# Base_logic_gate.net
KiCad netlist of a schematic drawn in Altium Designer
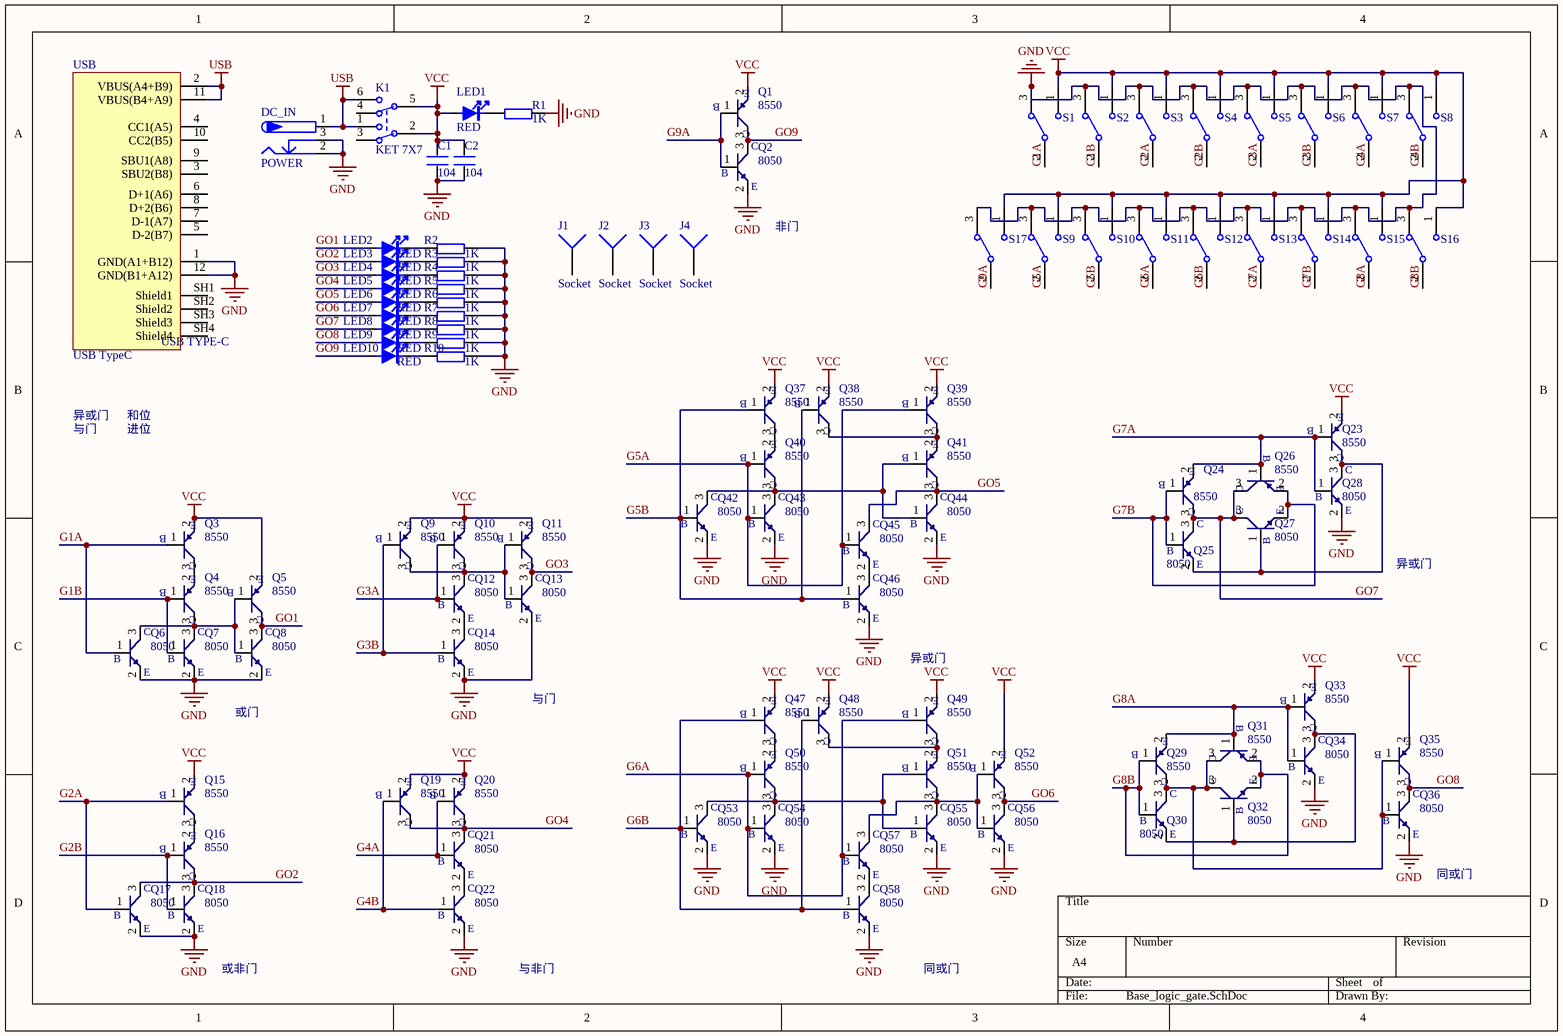
[diagram p0: Base_logic_gate.SchDoc]

(export (version "E")
  (design (tool "Eeschema 10.0.6"))
  (components
    (comp (ref "C1")
      (value "104")
      (footprint "C 0603_L")
      (libsource (lib "IMX6UL_ALPHA(底板)_V2.0") (part "C"))
    )
    (comp (ref "C2")
      (value "104")
      (footprint "C 0603_L")
      (libsource (lib "IMX6UL_ALPHA(底板)_V2.0") (part "C"))
    )
    (comp (ref "DC_IN")
      (value "POWER")
      (footprint "DC-005")
      (description "低压电源接口")
      (fields (field (name "版权归属") "源创客"))
      (libsource (lib "IMX6UL_ALPHA(底板)_V2.0") (part "P-DC"))
    )
    (comp (ref "J1")
      (value "Socket")
      (footprint "M3")
      (fields (field (name "PUBLISHER") "Altium Limited"))
      (libsource (lib "Miscellaneous Connectors") (part "Socket"))
    )
    (comp (ref "J2")
      (value "Socket")
      (footprint "M3")
      (fields (field (name "PUBLISHER") "Altium Limited"))
      (libsource (lib "Miscellaneous Connectors") (part "Socket"))
    )
    (comp (ref "J3")
      (value "Socket")
      (footprint "M3")
      (fields (field (name "PUBLISHER") "Altium Limited"))
      (libsource (lib "Miscellaneous Connectors") (part "Socket"))
    )
    (comp (ref "J4")
      (value "Socket")
      (footprint "M3")
      (fields (field (name "PUBLISHER") "Altium Limited"))
      (libsource (lib "Miscellaneous Connectors") (part "Socket"))
    )
    (comp (ref "K1")
      (value "KET 7X7")
      (footprint "KFT DIP-8X8")
      (description "7*7自锁开关")
      (fields (field (name "版权归属") "正点原子"))
      (libsource (lib "正点原子封装库V1.0") (part "KET 7X7"))
    )
    (comp (ref "LED1")
      (value "RED")
      (footprint "LED 0603B")
      (description "发光二极管")
      (libsource (lib "LovelessingSch") (part "LED"))
    )
    (comp (ref "LED2")
      (value "RED")
      (footprint "LED 0603B")
      (description "发光二极管")
      (libsource (lib "LovelessingSch") (part "LED"))
    )
    (comp (ref "LED3")
      (value "RED")
      (footprint "LED 0603B")
      (description "发光二极管")
      (libsource (lib "LovelessingSch") (part "LED"))
    )
    (comp (ref "LED4")
      (value "RED")
      (footprint "LED 0603B")
      (description "发光二极管")
      (libsource (lib "LovelessingSch") (part "LED"))
    )
    (comp (ref "LED5")
      (value "RED")
      (footprint "LED 0603B")
      (description "发光二极管")
      (libsource (lib "LovelessingSch") (part "LED"))
    )
    (comp (ref "LED6")
      (value "RED")
      (footprint "LED 0603B")
      (description "发光二极管")
      (libsource (lib "LovelessingSch") (part "LED"))
    )
    (comp (ref "LED7")
      (value "RED")
      (footprint "LED 0603B")
      (description "发光二极管")
      (libsource (lib "LovelessingSch") (part "LED"))
    )
    (comp (ref "LED8")
      (value "RED")
      (footprint "LED 0603B")
      (description "发光二极管")
      (libsource (lib "LovelessingSch") (part "LED"))
    )
    (comp (ref "LED9")
      (value "RED")
      (footprint "LED 0603B")
      (description "发光二极管")
      (libsource (lib "LovelessingSch") (part "LED"))
    )
    (comp (ref "LED10")
      (value "RED")
      (footprint "LED 0603B")
      (description "发光二极管")
      (libsource (lib "LovelessingSch") (part "LED"))
    )
    (comp (ref "Q1")
      (value "8550")
      (footprint "SOT23-3L")
      (libsource (lib "LovelessingSch") (part "8550PNP"))
    )
    (comp (ref "Q2")
      (value "8050")
      (footprint "SOT23-3L")
      (libsource (lib "LovelessingSch") (part "8050NPN"))
    )
    (comp (ref "Q3")
      (value "8550")
      (footprint "SOT23-3L")
      (libsource (lib "LovelessingSch") (part "8550PNP"))
    )
    (comp (ref "Q4")
      (value "8550")
      (footprint "SOT23-3L")
      (libsource (lib "LovelessingSch") (part "8550PNP"))
    )
    (comp (ref "Q5")
      (value "8550")
      (footprint "SOT23-3L")
      (libsource (lib "LovelessingSch") (part "8550PNP"))
    )
    (comp (ref "Q6")
      (value "8050")
      (footprint "SOT23-3L")
      (libsource (lib "LovelessingSch") (part "8050NPN"))
    )
    (comp (ref "Q7")
      (value "8050")
      (footprint "SOT23-3L")
      (libsource (lib "LovelessingSch") (part "8050NPN"))
    )
    (comp (ref "Q8")
      (value "8050")
      (footprint "SOT23-3L")
      (libsource (lib "LovelessingSch") (part "8050NPN"))
    )
    (comp (ref "Q9")
      (value "8550")
      (footprint "SOT23-3L")
      (libsource (lib "LovelessingSch") (part "8550PNP"))
    )
    (comp (ref "Q10")
      (value "8550")
      (footprint "SOT23-3L")
      (libsource (lib "LovelessingSch") (part "8550PNP"))
    )
    (comp (ref "Q11")
      (value "8550")
      (footprint "SOT23-3L")
      (libsource (lib "LovelessingSch") (part "8550PNP"))
    )
    (comp (ref "Q12")
      (value "8050")
      (footprint "SOT23-3L")
      (libsource (lib "LovelessingSch") (part "8050NPN"))
    )
    (comp (ref "Q13")
      (value "8050")
      (footprint "SOT23-3L")
      (libsource (lib "LovelessingSch") (part "8050NPN"))
    )
    (comp (ref "Q14")
      (value "8050")
      (footprint "SOT23-3L")
      (libsource (lib "LovelessingSch") (part "8050NPN"))
    )
    (comp (ref "Q15")
      (value "8550")
      (footprint "SOT23-3L")
      (libsource (lib "LovelessingSch") (part "8550PNP"))
    )
    (comp (ref "Q16")
      (value "8550")
      (footprint "SOT23-3L")
      (libsource (lib "LovelessingSch") (part "8550PNP"))
    )
    (comp (ref "Q17")
      (value "8050")
      (footprint "SOT23-3L")
      (libsource (lib "LovelessingSch") (part "8050NPN"))
    )
    (comp (ref "Q18")
      (value "8050")
      (footprint "SOT23-3L")
      (libsource (lib "LovelessingSch") (part "8050NPN"))
    )
    (comp (ref "Q19")
      (value "8550")
      (footprint "SOT23-3L")
      (libsource (lib "LovelessingSch") (part "8550PNP"))
    )
    (comp (ref "Q20")
      (value "8550")
      (footprint "SOT23-3L")
      (libsource (lib "LovelessingSch") (part "8550PNP"))
    )
    (comp (ref "Q21")
      (value "8050")
      (footprint "SOT23-3L")
      (libsource (lib "LovelessingSch") (part "8050NPN"))
    )
    (comp (ref "Q22")
      (value "8050")
      (footprint "SOT23-3L")
      (libsource (lib "LovelessingSch") (part "8050NPN"))
    )
    (comp (ref "Q23")
      (value "8550")
      (footprint "SOT23-3L")
      (libsource (lib "LovelessingSch") (part "8550PNP"))
    )
    (comp (ref "Q24")
      (value "8550")
      (footprint "SOT23-3L")
      (libsource (lib "LovelessingSch") (part "8550PNP"))
    )
    (comp (ref "Q25")
      (value "8050")
      (footprint "SOT23-3L")
      (libsource (lib "LovelessingSch") (part "8050NPN"))
    )
    (comp (ref "Q26")
      (value "8550")
      (footprint "SOT23-3L")
      (libsource (lib "LovelessingSch") (part "8550PNP"))
    )
    (comp (ref "Q27")
      (value "8050")
      (footprint "SOT23-3L")
      (libsource (lib "LovelessingSch") (part "8050NPN"))
    )
    (comp (ref "Q28")
      (value "8050")
      (footprint "SOT23-3L")
      (libsource (lib "LovelessingSch") (part "8050NPN"))
    )
    (comp (ref "Q29")
      (value "8550")
      (footprint "SOT23-3L")
      (libsource (lib "LovelessingSch") (part "8550PNP"))
    )
    (comp (ref "Q30")
      (value "8050")
      (footprint "SOT23-3L")
      (libsource (lib "LovelessingSch") (part "8050NPN"))
    )
    (comp (ref "Q31")
      (value "8550")
      (footprint "SOT23-3L")
      (libsource (lib "LovelessingSch") (part "8550PNP"))
    )
    (comp (ref "Q32")
      (value "8050")
      (footprint "SOT23-3L")
      (libsource (lib "LovelessingSch") (part "8050NPN"))
    )
    (comp (ref "Q33")
      (value "8550")
      (footprint "SOT23-3L")
      (libsource (lib "LovelessingSch") (part "8550PNP"))
    )
    (comp (ref "Q34")
      (value "8050")
      (footprint "SOT23-3L")
      (libsource (lib "LovelessingSch") (part "8050NPN"))
    )
    (comp (ref "Q35")
      (value "8550")
      (footprint "SOT23-3L")
      (libsource (lib "LovelessingSch") (part "8550PNP"))
    )
    (comp (ref "Q36")
      (value "8050")
      (footprint "SOT23-3L")
      (libsource (lib "LovelessingSch") (part "8050NPN"))
    )
    (comp (ref "Q37")
      (value "8550")
      (footprint "SOT23-3L")
      (libsource (lib "LovelessingSch") (part "8550PNP"))
    )
    (comp (ref "Q38")
      (value "8550")
      (footprint "SOT23-3L")
      (libsource (lib "LovelessingSch") (part "8550PNP"))
    )
    (comp (ref "Q39")
      (value "8550")
      (footprint "SOT23-3L")
      (libsource (lib "LovelessingSch") (part "8550PNP"))
    )
    (comp (ref "Q40")
      (value "8550")
      (footprint "SOT23-3L")
      (libsource (lib "LovelessingSch") (part "8550PNP"))
    )
    (comp (ref "Q41")
      (value "8550")
      (footprint "SOT23-3L")
      (libsource (lib "LovelessingSch") (part "8550PNP"))
    )
    (comp (ref "Q42")
      (value "8050")
      (footprint "SOT23-3L")
      (libsource (lib "LovelessingSch") (part "8050NPN"))
    )
    (comp (ref "Q43")
      (value "8050")
      (footprint "SOT23-3L")
      (libsource (lib "LovelessingSch") (part "8050NPN"))
    )
    (comp (ref "Q44")
      (value "8050")
      (footprint "SOT23-3L")
      (libsource (lib "LovelessingSch") (part "8050NPN"))
    )
    (comp (ref "Q45")
      (value "8050")
      (footprint "SOT23-3L")
      (libsource (lib "LovelessingSch") (part "8050NPN"))
    )
    (comp (ref "Q46")
      (value "8050")
      (footprint "SOT23-3L")
      (libsource (lib "LovelessingSch") (part "8050NPN"))
    )
    (comp (ref "Q47")
      (value "8550")
      (footprint "SOT23-3L")
      (libsource (lib "LovelessingSch") (part "8550PNP"))
    )
    (comp (ref "Q48")
      (value "8550")
      (footprint "SOT23-3L")
      (libsource (lib "LovelessingSch") (part "8550PNP"))
    )
    (comp (ref "Q49")
      (value "8550")
      (footprint "SOT23-3L")
      (libsource (lib "LovelessingSch") (part "8550PNP"))
    )
    (comp (ref "Q50")
      (value "8550")
      (footprint "SOT23-3L")
      (libsource (lib "LovelessingSch") (part "8550PNP"))
    )
    (comp (ref "Q51")
      (value "8550")
      (footprint "SOT23-3L")
      (libsource (lib "LovelessingSch") (part "8550PNP"))
    )
    (comp (ref "Q52")
      (value "8550")
      (footprint "SOT23-3L")
      (libsource (lib "LovelessingSch") (part "8550PNP"))
    )
    (comp (ref "Q53")
      (value "8050")
      (footprint "SOT23-3L")
      (libsource (lib "LovelessingSch") (part "8050NPN"))
    )
    (comp (ref "Q54")
      (value "8050")
      (footprint "SOT23-3L")
      (libsource (lib "LovelessingSch") (part "8050NPN"))
    )
    (comp (ref "Q55")
      (value "8050")
      (footprint "SOT23-3L")
      (libsource (lib "LovelessingSch") (part "8050NPN"))
    )
    (comp (ref "Q56")
      (value "8050")
      (footprint "SOT23-3L")
      (libsource (lib "LovelessingSch") (part "8050NPN"))
    )
    (comp (ref "Q57")
      (value "8050")
      (footprint "SOT23-3L")
      (libsource (lib "LovelessingSch") (part "8050NPN"))
    )
    (comp (ref "Q58")
      (value "8050")
      (footprint "SOT23-3L")
      (libsource (lib "LovelessingSch") (part "8050NPN"))
    )
    (comp (ref "R1") (value "1K") (footprint "R 0603_L") (libsource (lib "IMX6UL_ALPHA(底板)_V2.0") (part "R")))
    (comp (ref "R2") (value "1K") (footprint "R 0603_L") (libsource (lib "IMX6UL_ALPHA(底板)_V2.0") (part "R")))
    (comp (ref "R3") (value "1K") (footprint "R 0603_L") (libsource (lib "IMX6UL_ALPHA(底板)_V2.0") (part "R")))
    (comp (ref "R4") (value "1K") (footprint "R 0603_L") (libsource (lib "IMX6UL_ALPHA(底板)_V2.0") (part "R")))
    (comp (ref "R5") (value "1K") (footprint "R 0603_L") (libsource (lib "IMX6UL_ALPHA(底板)_V2.0") (part "R")))
    (comp (ref "R6") (value "1K") (footprint "R 0603_L") (libsource (lib "IMX6UL_ALPHA(底板)_V2.0") (part "R")))
    (comp (ref "R7") (value "1K") (footprint "R 0603_L") (libsource (lib "IMX6UL_ALPHA(底板)_V2.0") (part "R")))
    (comp (ref "R8") (value "1K") (footprint "R 0603_L") (libsource (lib "IMX6UL_ALPHA(底板)_V2.0") (part "R")))
    (comp (ref "R9") (value "1K") (footprint "R 0603_L") (libsource (lib "IMX6UL_ALPHA(底板)_V2.0") (part "R")))
    (comp (ref "R10")
      (value "1K")
      (footprint "R 0603_L")
      (libsource (lib "IMX6UL_ALPHA(底板)_V2.0") (part "R"))
    )
    (comp (ref "S1")
      (value "BUTTON_DIP3")
      (footprint "BTN8.8*4.6")
      (description "SPDT Subminiature Toggle Switch, Right Angle Mounting, Vertical Actuation")
      (fields (field (name "PUBLISHER") "Altium Limited"))
      (libsource (lib "Miscellaneous Devices") (part "SW-SPDT"))
    )
    (comp (ref "S2")
      (value "BUTTON_DIP3")
      (footprint "BTN8.8*4.6")
      (description "SPDT Subminiature Toggle Switch, Right Angle Mounting, Vertical Actuation")
      (fields (field (name "PUBLISHER") "Altium Limited"))
      (libsource (lib "Miscellaneous Devices") (part "SW-SPDT"))
    )
    (comp (ref "S3")
      (value "BUTTON_DIP3")
      (footprint "BTN8.8*4.6")
      (description "SPDT Subminiature Toggle Switch, Right Angle Mounting, Vertical Actuation")
      (fields (field (name "PUBLISHER") "Altium Limited"))
      (libsource (lib "Miscellaneous Devices") (part "SW-SPDT"))
    )
    (comp (ref "S4")
      (value "BUTTON_DIP3")
      (footprint "BTN8.8*4.6")
      (description "SPDT Subminiature Toggle Switch, Right Angle Mounting, Vertical Actuation")
      (fields (field (name "PUBLISHER") "Altium Limited"))
      (libsource (lib "Miscellaneous Devices") (part "SW-SPDT"))
    )
    (comp (ref "S5")
      (value "BUTTON_DIP3")
      (footprint "BTN8.8*4.6")
      (description "SPDT Subminiature Toggle Switch, Right Angle Mounting, Vertical Actuation")
      (fields (field (name "PUBLISHER") "Altium Limited"))
      (libsource (lib "Miscellaneous Devices") (part "SW-SPDT"))
    )
    (comp (ref "S6")
      (value "BUTTON_DIP3")
      (footprint "BTN8.8*4.6")
      (description "SPDT Subminiature Toggle Switch, Right Angle Mounting, Vertical Actuation")
      (fields (field (name "PUBLISHER") "Altium Limited"))
      (libsource (lib "Miscellaneous Devices") (part "SW-SPDT"))
    )
    (comp (ref "S7")
      (value "BUTTON_DIP3")
      (footprint "BTN8.8*4.6")
      (description "SPDT Subminiature Toggle Switch, Right Angle Mounting, Vertical Actuation")
      (fields (field (name "PUBLISHER") "Altium Limited"))
      (libsource (lib "Miscellaneous Devices") (part "SW-SPDT"))
    )
    (comp (ref "S8")
      (value "BUTTON_DIP3")
      (footprint "BTN8.8*4.6")
      (description "SPDT Subminiature Toggle Switch, Right Angle Mounting, Vertical Actuation")
      (fields (field (name "PUBLISHER") "Altium Limited"))
      (libsource (lib "Miscellaneous Devices") (part "SW-SPDT"))
    )
    (comp (ref "S9")
      (value "BUTTON_DIP3")
      (footprint "BTN8.8*4.6")
      (description "SPDT Subminiature Toggle Switch, Right Angle Mounting, Vertical Actuation")
      (fields (field (name "PUBLISHER") "Altium Limited"))
      (libsource (lib "Miscellaneous Devices") (part "SW-SPDT"))
    )
    (comp (ref "S10")
      (value "BUTTON_DIP3")
      (footprint "BTN8.8*4.6")
      (description "SPDT Subminiature Toggle Switch, Right Angle Mounting, Vertical Actuation")
      (fields (field (name "PUBLISHER") "Altium Limited"))
      (libsource (lib "Miscellaneous Devices") (part "SW-SPDT"))
    )
    (comp (ref "S11")
      (value "BUTTON_DIP3")
      (footprint "BTN8.8*4.6")
      (description "SPDT Subminiature Toggle Switch, Right Angle Mounting, Vertical Actuation")
      (fields (field (name "PUBLISHER") "Altium Limited"))
      (libsource (lib "Miscellaneous Devices") (part "SW-SPDT"))
    )
    (comp (ref "S12")
      (value "BUTTON_DIP3")
      (footprint "BTN8.8*4.6")
      (description "SPDT Subminiature Toggle Switch, Right Angle Mounting, Vertical Actuation")
      (fields (field (name "PUBLISHER") "Altium Limited"))
      (libsource (lib "Miscellaneous Devices") (part "SW-SPDT"))
    )
    (comp (ref "S13")
      (value "BUTTON_DIP3")
      (footprint "BTN8.8*4.6")
      (description "SPDT Subminiature Toggle Switch, Right Angle Mounting, Vertical Actuation")
      (fields (field (name "PUBLISHER") "Altium Limited"))
      (libsource (lib "Miscellaneous Devices") (part "SW-SPDT"))
    )
    (comp (ref "S14")
      (value "BUTTON_DIP3")
      (footprint "BTN8.8*4.6")
      (description "SPDT Subminiature Toggle Switch, Right Angle Mounting, Vertical Actuation")
      (fields (field (name "PUBLISHER") "Altium Limited"))
      (libsource (lib "Miscellaneous Devices") (part "SW-SPDT"))
    )
    (comp (ref "S15")
      (value "BUTTON_DIP3")
      (footprint "BTN8.8*4.6")
      (description "SPDT Subminiature Toggle Switch, Right Angle Mounting, Vertical Actuation")
      (fields (field (name "PUBLISHER") "Altium Limited"))
      (libsource (lib "Miscellaneous Devices") (part "SW-SPDT"))
    )
    (comp (ref "S16")
      (value "BUTTON_DIP3")
      (footprint "BTN8.8*4.6")
      (description "SPDT Subminiature Toggle Switch, Right Angle Mounting, Vertical Actuation")
      (fields (field (name "PUBLISHER") "Altium Limited"))
      (libsource (lib "Miscellaneous Devices") (part "SW-SPDT"))
    )
    (comp (ref "S17")
      (value "BUTTON_DIP3")
      (footprint "BTN8.8*4.6")
      (description "SPDT Subminiature Toggle Switch, Right Angle Mounting, Vertical Actuation")
      (fields (field (name "PUBLISHER") "Altium Limited"))
      (libsource (lib "Miscellaneous Devices") (part "SW-SPDT"))
    )
    (comp (ref "USB")
      (value "USB TypeC")
      (footprint "USB Type-C")
      (description "12P TypeC 母座")
      (fields (field (name "版权归属") "正点原子"))
      (libsource (lib "正点原子封装库V1.0") (part "USB 2.0 Type C"))
    )
  )
  (nets
    (net (code "1") (name "/G1A") (class "Default")
      (node (ref "Q3") (pin "1") (pinfunction "B_1") (pintype "passive"))
      (node (ref "Q6") (pin "1") (pinfunction "B_1") (pintype "passive"))
      (node (ref "S1") (pin "2") (pinfunction "2_2") (pintype "passive"))
    )
    (net (code "2") (name "/G1B") (class "Default")
      (node (ref "Q4") (pin "1") (pinfunction "B_1") (pintype "passive"))
      (node (ref "Q7") (pin "1") (pinfunction "B_1") (pintype "passive"))
      (node (ref "S2") (pin "2") (pinfunction "2_2") (pintype "passive"))
    )
    (net (code "3") (name "/G2A") (class "Default")
      (node (ref "Q15") (pin "1") (pinfunction "B_1") (pintype "passive"))
      (node (ref "Q17") (pin "1") (pinfunction "B_1") (pintype "passive"))
      (node (ref "S3") (pin "2") (pinfunction "2_2") (pintype "passive"))
    )
    (net (code "4") (name "/G2B") (class "Default")
      (node (ref "Q16") (pin "1") (pinfunction "B_1") (pintype "passive"))
      (node (ref "Q18") (pin "1") (pinfunction "B_1") (pintype "passive"))
      (node (ref "S4") (pin "2") (pinfunction "2_2") (pintype "passive"))
    )
    (net (code "5") (name "/G3A") (class "Default")
      (node (ref "Q10") (pin "1") (pinfunction "B_1") (pintype "passive"))
      (node (ref "Q12") (pin "1") (pinfunction "B_1") (pintype "passive"))
      (node (ref "S5") (pin "2") (pinfunction "2_2") (pintype "passive"))
    )
    (net (code "6") (name "/G3B") (class "Default")
      (node (ref "Q14") (pin "1") (pinfunction "B_1") (pintype "passive"))
      (node (ref "Q9") (pin "1") (pinfunction "B_1") (pintype "passive"))
      (node (ref "S6") (pin "2") (pinfunction "2_2") (pintype "passive"))
    )
    (net (code "7") (name "/G4A") (class "Default")
      (node (ref "Q20") (pin "1") (pinfunction "B_1") (pintype "passive"))
      (node (ref "Q21") (pin "1") (pinfunction "B_1") (pintype "passive"))
      (node (ref "S7") (pin "2") (pinfunction "2_2") (pintype "passive"))
    )
    (net (code "8") (name "/G4B") (class "Default")
      (node (ref "Q19") (pin "1") (pinfunction "B_1") (pintype "passive"))
      (node (ref "Q22") (pin "1") (pinfunction "B_1") (pintype "passive"))
      (node (ref "S8") (pin "2") (pinfunction "2_2") (pintype "passive"))
    )
    (net (code "9") (name "/G5A") (class "Default")
      (node (ref "Q39") (pin "1") (pinfunction "B_1") (pintype "passive"))
      (node (ref "Q40") (pin "1") (pinfunction "B_1") (pintype "passive"))
      (node (ref "Q43") (pin "1") (pinfunction "B_1") (pintype "passive"))
      (node (ref "Q45") (pin "1") (pinfunction "B_1") (pintype "passive"))
      (node (ref "S9") (pin "2") (pinfunction "2_2") (pintype "passive"))
    )
    (net (code "10") (name "/G5B") (class "Default")
      (node (ref "Q37") (pin "1") (pinfunction "B_1") (pintype "passive"))
      (node (ref "Q38") (pin "1") (pinfunction "B_1") (pintype "passive"))
      (node (ref "Q42") (pin "1") (pinfunction "B_1") (pintype "passive"))
      (node (ref "Q46") (pin "1") (pinfunction "B_1") (pintype "passive"))
      (node (ref "S10") (pin "2") (pinfunction "2_2") (pintype "passive"))
    )
    (net (code "11") (name "/G6A") (class "Default")
      (node (ref "Q49") (pin "1") (pinfunction "B_1") (pintype "passive"))
      (node (ref "Q50") (pin "1") (pinfunction "B_1") (pintype "passive"))
      (node (ref "Q54") (pin "1") (pinfunction "B_1") (pintype "passive"))
      (node (ref "Q57") (pin "1") (pinfunction "B_1") (pintype "passive"))
      (node (ref "S11") (pin "2") (pinfunction "2_2") (pintype "passive"))
    )
    (net (code "12") (name "/G6B") (class "Default")
      (node (ref "Q47") (pin "1") (pinfunction "B_1") (pintype "passive"))
      (node (ref "Q48") (pin "1") (pinfunction "B_1") (pintype "passive"))
      (node (ref "Q53") (pin "1") (pinfunction "B_1") (pintype "passive"))
      (node (ref "Q58") (pin "1") (pinfunction "B_1") (pintype "passive"))
      (node (ref "S12") (pin "2") (pinfunction "2_2") (pintype "passive"))
    )
    (net (code "13") (name "/G7A") (class "Default")
      (node (ref "Q23") (pin "1") (pinfunction "B_1") (pintype "passive"))
      (node (ref "Q24") (pin "2") (pinfunction "E_2") (pintype "passive"))
      (node (ref "Q26") (pin "1") (pinfunction "B_1") (pintype "passive"))
      (node (ref "Q28") (pin "1") (pinfunction "B_1") (pintype "passive"))
      (node (ref "S13") (pin "2") (pinfunction "2_2") (pintype "passive"))
    )
    (net (code "14") (name "/G7B") (class "Default")
      (node (ref "Q24") (pin "1") (pinfunction "B_1") (pintype "passive"))
      (node (ref "Q25") (pin "1") (pinfunction "B_1") (pintype "passive"))
      (node (ref "Q26") (pin "2") (pinfunction "E_2") (pintype "passive"))
      (node (ref "Q27") (pin "2") (pinfunction "E_2") (pintype "passive"))
      (node (ref "S14") (pin "2") (pinfunction "2_2") (pintype "passive"))
    )
    (net (code "15") (name "/G8A") (class "Default")
      (node (ref "Q29") (pin "2") (pinfunction "E_2") (pintype "passive"))
      (node (ref "Q31") (pin "1") (pinfunction "B_1") (pintype "passive"))
      (node (ref "Q33") (pin "1") (pinfunction "B_1") (pintype "passive"))
      (node (ref "Q34") (pin "1") (pinfunction "B_1") (pintype "passive"))
      (node (ref "S15") (pin "2") (pinfunction "2_2") (pintype "passive"))
    )
    (net (code "16") (name "/G8B") (class "Default")
      (node (ref "Q29") (pin "1") (pinfunction "B_1") (pintype "passive"))
      (node (ref "Q30") (pin "1") (pinfunction "B_1") (pintype "passive"))
      (node (ref "Q31") (pin "2") (pinfunction "E_2") (pintype "passive"))
      (node (ref "Q32") (pin "2") (pinfunction "E_2") (pintype "passive"))
      (node (ref "S16") (pin "2") (pinfunction "2_2") (pintype "passive"))
    )
    (net (code "17") (name "/G9A") (class "Default")
      (node (ref "Q1") (pin "1") (pinfunction "B_1") (pintype "passive"))
      (node (ref "Q2") (pin "1") (pinfunction "B_1") (pintype "passive"))
      (node (ref "S17") (pin "2") (pinfunction "2_2") (pintype "passive"))
    )
    (net (code "18") (name "/GO1") (class "Default")
      (node (ref "LED2") (pin "1") (pinfunction "1_1") (pintype "passive"))
      (node (ref "Q5") (pin "3") (pinfunction "C_3") (pintype "passive"))
      (node (ref "Q8") (pin "3") (pinfunction "C_3") (pintype "passive"))
    )
    (net (code "19") (name "/GO2") (class "Default")
      (node (ref "LED3") (pin "1") (pinfunction "1_1") (pintype "passive"))
      (node (ref "Q16") (pin "3") (pinfunction "C_3") (pintype "passive"))
      (node (ref "Q17") (pin "3") (pinfunction "C_3") (pintype "passive"))
      (node (ref "Q18") (pin "3") (pinfunction "C_3") (pintype "passive"))
    )
    (net (code "20") (name "/GO3") (class "Default")
      (node (ref "LED4") (pin "1") (pinfunction "1_1") (pintype "passive"))
      (node (ref "Q11") (pin "3") (pinfunction "C_3") (pintype "passive"))
      (node (ref "Q13") (pin "3") (pinfunction "C_3") (pintype "passive"))
    )
    (net (code "21") (name "/GO4") (class "Default")
      (node (ref "LED5") (pin "1") (pinfunction "1_1") (pintype "passive"))
      (node (ref "Q19") (pin "3") (pinfunction "C_3") (pintype "passive"))
      (node (ref "Q20") (pin "3") (pinfunction "C_3") (pintype "passive"))
      (node (ref "Q21") (pin "3") (pinfunction "C_3") (pintype "passive"))
    )
    (net (code "22") (name "/GO5") (class "Default")
      (node (ref "LED6") (pin "1") (pinfunction "1_1") (pintype "passive"))
      (node (ref "Q41") (pin "3") (pinfunction "C_3") (pintype "passive"))
      (node (ref "Q44") (pin "3") (pinfunction "C_3") (pintype "passive"))
      (node (ref "Q45") (pin "3") (pinfunction "C_3") (pintype "passive"))
    )
    (net (code "23") (name "/GO6") (class "Default")
      (node (ref "LED7") (pin "1") (pinfunction "1_1") (pintype "passive"))
      (node (ref "Q52") (pin "3") (pinfunction "C_3") (pintype "passive"))
      (node (ref "Q56") (pin "3") (pinfunction "C_3") (pintype "passive"))
    )
    (net (code "24") (name "/GO7") (class "Default")
      (node (ref "LED8") (pin "1") (pinfunction "1_1") (pintype "passive"))
      (node (ref "Q24") (pin "3") (pinfunction "C_3") (pintype "passive"))
      (node (ref "Q25") (pin "3") (pinfunction "C_3") (pintype "passive"))
      (node (ref "Q26") (pin "3") (pinfunction "C_3") (pintype "passive"))
      (node (ref "Q27") (pin "3") (pinfunction "C_3") (pintype "passive"))
    )
    (net (code "25") (name "/GO8") (class "Default")
      (node (ref "LED9") (pin "1") (pinfunction "1_1") (pintype "passive"))
      (node (ref "Q35") (pin "3") (pinfunction "C_3") (pintype "passive"))
      (node (ref "Q36") (pin "3") (pinfunction "C_3") (pintype "passive"))
    )
    (net (code "26") (name "/GO9") (class "Default")
      (node (ref "LED10") (pin "1") (pinfunction "1_1") (pintype "passive"))
      (node (ref "Q1") (pin "3") (pinfunction "C_3") (pintype "passive"))
      (node (ref "Q2") (pin "3") (pinfunction "C_3") (pintype "passive"))
    )
    (net (code "27") (name "GND") (class "Default")
      (node (ref "C1") (pin "1") (pintype "passive"))
      (node (ref "C2") (pin "1") (pintype "passive"))
      (node (ref "DC_IN") (pin "2") (pintype "power_in"))
      (node (ref "DC_IN") (pin "3") (pintype "power_in"))
      (node (ref "Q13") (pin "2") (pinfunction "E_2") (pintype "passive"))
      (node (ref "Q14") (pin "2") (pinfunction "E_2") (pintype "passive"))
      (node (ref "Q17") (pin "2") (pinfunction "E_2") (pintype "passive"))
      (node (ref "Q18") (pin "2") (pinfunction "E_2") (pintype "passive"))
      (node (ref "Q2") (pin "2") (pinfunction "E_2") (pintype "passive"))
      (node (ref "Q22") (pin "2") (pinfunction "E_2") (pintype "passive"))
      (node (ref "Q28") (pin "2") (pinfunction "E_2") (pintype "passive"))
      (node (ref "Q34") (pin "2") (pinfunction "E_2") (pintype "passive"))
      (node (ref "Q36") (pin "2") (pinfunction "E_2") (pintype "passive"))
      (node (ref "Q42") (pin "2") (pinfunction "E_2") (pintype "passive"))
      (node (ref "Q43") (pin "2") (pinfunction "E_2") (pintype "passive"))
      (node (ref "Q44") (pin "2") (pinfunction "E_2") (pintype "passive"))
      (node (ref "Q46") (pin "2") (pinfunction "E_2") (pintype "passive"))
      (node (ref "Q53") (pin "2") (pinfunction "E_2") (pintype "passive"))
      (node (ref "Q54") (pin "2") (pinfunction "E_2") (pintype "passive"))
      (node (ref "Q55") (pin "2") (pinfunction "E_2") (pintype "passive"))
      (node (ref "Q56") (pin "2") (pinfunction "E_2") (pintype "passive"))
      (node (ref "Q58") (pin "2") (pinfunction "E_2") (pintype "passive"))
      (node (ref "Q6") (pin "2") (pinfunction "E_2") (pintype "passive"))
      (node (ref "Q7") (pin "2") (pinfunction "E_2") (pintype "passive"))
      (node (ref "Q8") (pin "2") (pinfunction "E_2") (pintype "passive"))
      (node (ref "R1") (pin "2") (pintype "passive"))
      (node (ref "R10") (pin "2") (pintype "passive"))
      (node (ref "R2") (pin "2") (pintype "passive"))
      (node (ref "R3") (pin "2") (pintype "passive"))
      (node (ref "R4") (pin "2") (pintype "passive"))
      (node (ref "R5") (pin "2") (pintype "passive"))
      (node (ref "R6") (pin "2") (pintype "passive"))
      (node (ref "R7") (pin "2") (pintype "passive"))
      (node (ref "R8") (pin "2") (pintype "passive"))
      (node (ref "R9") (pin "2") (pintype "passive"))
      (node (ref "S1") (pin "3") (pinfunction "3_3") (pintype "passive"))
      (node (ref "S10") (pin "3") (pinfunction "3_3") (pintype "passive"))
      (node (ref "S11") (pin "3") (pinfunction "3_3") (pintype "passive"))
      (node (ref "S12") (pin "3") (pinfunction "3_3") (pintype "passive"))
      (node (ref "S13") (pin "3") (pinfunction "3_3") (pintype "passive"))
      (node (ref "S14") (pin "3") (pinfunction "3_3") (pintype "passive"))
      (node (ref "S15") (pin "3") (pinfunction "3_3") (pintype "passive"))
      (node (ref "S16") (pin "3") (pinfunction "3_3") (pintype "passive"))
      (node (ref "S17") (pin "3") (pinfunction "3_3") (pintype "passive"))
      (node (ref "S2") (pin "3") (pinfunction "3_3") (pintype "passive"))
      (node (ref "S3") (pin "3") (pinfunction "3_3") (pintype "passive"))
      (node (ref "S4") (pin "3") (pinfunction "3_3") (pintype "passive"))
      (node (ref "S5") (pin "3") (pinfunction "3_3") (pintype "passive"))
      (node (ref "S6") (pin "3") (pinfunction "3_3") (pintype "passive"))
      (node (ref "S7") (pin "3") (pinfunction "3_3") (pintype "passive"))
      (node (ref "S8") (pin "3") (pinfunction "3_3") (pintype "passive"))
      (node (ref "S9") (pin "3") (pinfunction "3_3") (pintype "passive"))
      (node (ref "USB") (pin "1") (pinfunction "GND(A1+B12)_1") (pintype "passive"))
      (node (ref "USB") (pin "12") (pinfunction "GND(B1+A12)_12") (pintype "passive"))
    )
    (net (code "28") (name "Net-(LED1-Pad2)") (class "Default")
      (node (ref "LED1") (pin "2") (pinfunction "2_2") (pintype "passive"))
      (node (ref "R1") (pin "1") (pintype "passive"))
    )
    (net (code "29") (name "Net-(LED2-Pad2)") (class "Default")
      (node (ref "LED2") (pin "2") (pinfunction "2_2") (pintype "passive"))
      (node (ref "R2") (pin "1") (pintype "passive"))
    )
    (net (code "30") (name "Net-(LED3-Pad2)") (class "Default")
      (node (ref "LED3") (pin "2") (pinfunction "2_2") (pintype "passive"))
      (node (ref "R3") (pin "1") (pintype "passive"))
    )
    (net (code "31") (name "Net-(LED4-Pad2)") (class "Default")
      (node (ref "LED4") (pin "2") (pinfunction "2_2") (pintype "passive"))
      (node (ref "R4") (pin "1") (pintype "passive"))
    )
    (net (code "32") (name "Net-(LED5-Pad2)") (class "Default")
      (node (ref "LED5") (pin "2") (pinfunction "2_2") (pintype "passive"))
      (node (ref "R5") (pin "1") (pintype "passive"))
    )
    (net (code "33") (name "Net-(LED6-Pad2)") (class "Default")
      (node (ref "LED6") (pin "2") (pinfunction "2_2") (pintype "passive"))
      (node (ref "R6") (pin "1") (pintype "passive"))
    )
    (net (code "34") (name "Net-(LED7-Pad2)") (class "Default")
      (node (ref "LED7") (pin "2") (pinfunction "2_2") (pintype "passive"))
      (node (ref "R7") (pin "1") (pintype "passive"))
    )
    (net (code "35") (name "Net-(LED8-Pad2)") (class "Default")
      (node (ref "LED8") (pin "2") (pinfunction "2_2") (pintype "passive"))
      (node (ref "R8") (pin "1") (pintype "passive"))
    )
    (net (code "36") (name "Net-(LED9-Pad2)") (class "Default")
      (node (ref "LED9") (pin "2") (pinfunction "2_2") (pintype "passive"))
      (node (ref "R9") (pin "1") (pintype "passive"))
    )
    (net (code "37") (name "Net-(LED10-Pad2)") (class "Default")
      (node (ref "LED10") (pin "2") (pinfunction "2_2") (pintype "passive"))
      (node (ref "R10") (pin "1") (pintype "passive"))
    )
    (net (code "38") (name "Net-(Q3-C)") (class "Default")
      (node (ref "Q3") (pin "3") (pinfunction "C_3") (pintype "passive"))
      (node (ref "Q4") (pin "2") (pinfunction "E_2") (pintype "passive"))
    )
    (net (code "39") (name "Net-(Q4-C)") (class "Default")
      (node (ref "Q4") (pin "3") (pinfunction "C_3") (pintype "passive"))
      (node (ref "Q5") (pin "1") (pinfunction "B_1") (pintype "passive"))
      (node (ref "Q6") (pin "3") (pinfunction "C_3") (pintype "passive"))
      (node (ref "Q7") (pin "3") (pinfunction "C_3") (pintype "passive"))
      (node (ref "Q8") (pin "1") (pinfunction "B_1") (pintype "passive"))
    )
    (net (code "40") (name "Net-(Q10-C)") (class "Default")
      (node (ref "Q10") (pin "3") (pinfunction "C_3") (pintype "passive"))
      (node (ref "Q11") (pin "1") (pinfunction "B_1") (pintype "passive"))
      (node (ref "Q12") (pin "3") (pinfunction "C_3") (pintype "passive"))
      (node (ref "Q13") (pin "1") (pinfunction "B_1") (pintype "passive"))
      (node (ref "Q9") (pin "3") (pinfunction "C_3") (pintype "passive"))
    )
    (net (code "41") (name "Net-(Q12-E)") (class "Default")
      (node (ref "Q12") (pin "2") (pinfunction "E_2") (pintype "passive"))
      (node (ref "Q14") (pin "3") (pinfunction "C_3") (pintype "passive"))
    )
    (net (code "42") (name "Net-(Q15-C)") (class "Default")
      (node (ref "Q15") (pin "3") (pinfunction "C_3") (pintype "passive"))
      (node (ref "Q16") (pin "2") (pinfunction "E_2") (pintype "passive"))
    )
    (net (code "43") (name "Net-(Q21-E)") (class "Default")
      (node (ref "Q21") (pin "2") (pinfunction "E_2") (pintype "passive"))
      (node (ref "Q22") (pin "3") (pinfunction "C_3") (pintype "passive"))
    )
    (net (code "44") (name "Net-(Q23-C)") (class "Default")
      (node (ref "Q23") (pin "3") (pinfunction "C_3") (pintype "passive"))
      (node (ref "Q25") (pin "2") (pinfunction "E_2") (pintype "passive"))
      (node (ref "Q27") (pin "1") (pinfunction "B_1") (pintype "passive"))
      (node (ref "Q28") (pin "3") (pinfunction "C_3") (pintype "passive"))
    )
    (net (code "45") (name "Net-(Q29-C)") (class "Default")
      (node (ref "Q29") (pin "3") (pinfunction "C_3") (pintype "passive"))
      (node (ref "Q30") (pin "3") (pinfunction "C_3") (pintype "passive"))
      (node (ref "Q31") (pin "3") (pinfunction "C_3") (pintype "passive"))
      (node (ref "Q32") (pin "3") (pinfunction "C_3") (pintype "passive"))
      (node (ref "Q35") (pin "1") (pinfunction "B_1") (pintype "passive"))
      (node (ref "Q36") (pin "1") (pinfunction "B_1") (pintype "passive"))
    )
    (net (code "46") (name "Net-(Q30-E)") (class "Default")
      (node (ref "Q30") (pin "2") (pinfunction "E_2") (pintype "passive"))
      (node (ref "Q32") (pin "1") (pinfunction "B_1") (pintype "passive"))
      (node (ref "Q33") (pin "3") (pinfunction "C_3") (pintype "passive"))
      (node (ref "Q34") (pin "3") (pinfunction "C_3") (pintype "passive"))
    )
    (net (code "47") (name "Net-(Q37-C)") (class "Default")
      (node (ref "Q37") (pin "3") (pinfunction "C_3") (pintype "passive"))
      (node (ref "Q40") (pin "2") (pinfunction "E_2") (pintype "passive"))
    )
    (net (code "48") (name "Net-(Q38-C)") (class "Default")
      (node (ref "Q38") (pin "3") (pinfunction "C_3") (pintype "passive"))
      (node (ref "Q39") (pin "3") (pinfunction "C_3") (pintype "passive"))
      (node (ref "Q41") (pin "2") (pinfunction "E_2") (pintype "passive"))
    )
    (net (code "49") (name "Net-(Q40-C)") (class "Default")
      (node (ref "Q40") (pin "3") (pinfunction "C_3") (pintype "passive"))
      (node (ref "Q41") (pin "1") (pinfunction "B_1") (pintype "passive"))
      (node (ref "Q42") (pin "3") (pinfunction "C_3") (pintype "passive"))
      (node (ref "Q43") (pin "3") (pinfunction "C_3") (pintype "passive"))
      (node (ref "Q44") (pin "1") (pinfunction "B_1") (pintype "passive"))
    )
    (net (code "50") (name "Net-(Q45-E)") (class "Default")
      (node (ref "Q45") (pin "2") (pinfunction "E_2") (pintype "passive"))
      (node (ref "Q46") (pin "3") (pinfunction "C_3") (pintype "passive"))
    )
    (net (code "51") (name "Net-(Q47-C)") (class "Default")
      (node (ref "Q47") (pin "3") (pinfunction "C_3") (pintype "passive"))
      (node (ref "Q50") (pin "2") (pinfunction "E_2") (pintype "passive"))
    )
    (net (code "52") (name "Net-(Q48-C)") (class "Default")
      (node (ref "Q48") (pin "3") (pinfunction "C_3") (pintype "passive"))
      (node (ref "Q49") (pin "3") (pinfunction "C_3") (pintype "passive"))
      (node (ref "Q51") (pin "2") (pinfunction "E_2") (pintype "passive"))
    )
    (net (code "53") (name "Net-(Q50-C)") (class "Default")
      (node (ref "Q50") (pin "3") (pinfunction "C_3") (pintype "passive"))
      (node (ref "Q51") (pin "1") (pinfunction "B_1") (pintype "passive"))
      (node (ref "Q53") (pin "3") (pinfunction "C_3") (pintype "passive"))
      (node (ref "Q54") (pin "3") (pinfunction "C_3") (pintype "passive"))
      (node (ref "Q55") (pin "1") (pinfunction "B_1") (pintype "passive"))
    )
    (net (code "54") (name "Net-(Q51-C)") (class "Default")
      (node (ref "Q51") (pin "3") (pinfunction "C_3") (pintype "passive"))
      (node (ref "Q52") (pin "1") (pinfunction "B_1") (pintype "passive"))
      (node (ref "Q55") (pin "3") (pinfunction "C_3") (pintype "passive"))
      (node (ref "Q56") (pin "1") (pinfunction "B_1") (pintype "passive"))
      (node (ref "Q57") (pin "3") (pinfunction "C_3") (pintype "passive"))
    )
    (net (code "55") (name "Net-(Q57-E)") (class "Default")
      (node (ref "Q57") (pin "2") (pinfunction "E_2") (pintype "passive"))
      (node (ref "Q58") (pin "3") (pinfunction "C_3") (pintype "passive"))
    )
    (net (code "56") (name "USB") (class "Default")
      (node (ref "DC_IN") (pin "1") (pintype "power_in"))
      (node (ref "K1") (pin "1") (pinfunction "NC1_1") (pintype "passive"))
      (node (ref "K1") (pin "6") (pinfunction "NC2_6") (pintype "passive"))
      (node (ref "USB") (pin "11") (pinfunction "VBUS(B4+A9)_11") (pintype "passive"))
      (node (ref "USB") (pin "2") (pinfunction "VBUS(A4+B9)_2") (pintype "passive"))
    )
    (net (code "57") (name "VCC") (class "Default")
      (node (ref "C1") (pin "2") (pintype "passive"))
      (node (ref "C2") (pin "2") (pintype "passive"))
      (node (ref "K1") (pin "2") (pinfunction "COM1_2") (pintype "passive"))
      (node (ref "K1") (pin "5") (pinfunction "COM2_5") (pintype "passive"))
      (node (ref "LED1") (pin "1") (pinfunction "1_1") (pintype "passive"))
      (node (ref "Q1") (pin "2") (pinfunction "E_2") (pintype "passive"))
      (node (ref "Q10") (pin "2") (pinfunction "E_2") (pintype "passive"))
      (node (ref "Q11") (pin "2") (pinfunction "E_2") (pintype "passive"))
      (node (ref "Q15") (pin "2") (pinfunction "E_2") (pintype "passive"))
      (node (ref "Q19") (pin "2") (pinfunction "E_2") (pintype "passive"))
      (node (ref "Q20") (pin "2") (pinfunction "E_2") (pintype "passive"))
      (node (ref "Q23") (pin "2") (pinfunction "E_2") (pintype "passive"))
      (node (ref "Q3") (pin "2") (pinfunction "E_2") (pintype "passive"))
      (node (ref "Q33") (pin "2") (pinfunction "E_2") (pintype "passive"))
      (node (ref "Q35") (pin "2") (pinfunction "E_2") (pintype "passive"))
      (node (ref "Q37") (pin "2") (pinfunction "E_2") (pintype "passive"))
      (node (ref "Q38") (pin "2") (pinfunction "E_2") (pintype "passive"))
      (node (ref "Q39") (pin "2") (pinfunction "E_2") (pintype "passive"))
      (node (ref "Q47") (pin "2") (pinfunction "E_2") (pintype "passive"))
      (node (ref "Q48") (pin "2") (pinfunction "E_2") (pintype "passive"))
      (node (ref "Q49") (pin "2") (pinfunction "E_2") (pintype "passive"))
      (node (ref "Q5") (pin "2") (pinfunction "E_2") (pintype "passive"))
      (node (ref "Q52") (pin "2") (pinfunction "E_2") (pintype "passive"))
      (node (ref "Q9") (pin "2") (pinfunction "E_2") (pintype "passive"))
      (node (ref "S1") (pin "1") (pinfunction "1_1") (pintype "passive"))
      (node (ref "S10") (pin "1") (pinfunction "1_1") (pintype "passive"))
      (node (ref "S11") (pin "1") (pinfunction "1_1") (pintype "passive"))
      (node (ref "S12") (pin "1") (pinfunction "1_1") (pintype "passive"))
      (node (ref "S13") (pin "1") (pinfunction "1_1") (pintype "passive"))
      (node (ref "S14") (pin "1") (pinfunction "1_1") (pintype "passive"))
      (node (ref "S15") (pin "1") (pinfunction "1_1") (pintype "passive"))
      (node (ref "S16") (pin "1") (pinfunction "1_1") (pintype "passive"))
      (node (ref "S17") (pin "1") (pinfunction "1_1") (pintype "passive"))
      (node (ref "S2") (pin "1") (pinfunction "1_1") (pintype "passive"))
      (node (ref "S3") (pin "1") (pinfunction "1_1") (pintype "passive"))
      (node (ref "S4") (pin "1") (pinfunction "1_1") (pintype "passive"))
      (node (ref "S5") (pin "1") (pinfunction "1_1") (pintype "passive"))
      (node (ref "S6") (pin "1") (pinfunction "1_1") (pintype "passive"))
      (node (ref "S7") (pin "1") (pinfunction "1_1") (pintype "passive"))
      (node (ref "S8") (pin "1") (pinfunction "1_1") (pintype "passive"))
      (node (ref "S9") (pin "1") (pinfunction "1_1") (pintype "passive"))
    )
    (net (code "58") (name "unconnected-(J1-Pad1)") (class "Default")
      (node (ref "J1") (pin "1") (pinfunction "1_1") (pintype "passive"))
    )
    (net (code "59") (name "unconnected-(J2-Pad1)") (class "Default")
      (node (ref "J2") (pin "1") (pinfunction "1_1") (pintype "passive"))
    )
    (net (code "60") (name "unconnected-(J3-Pad1)") (class "Default")
      (node (ref "J3") (pin "1") (pinfunction "1_1") (pintype "passive"))
    )
    (net (code "61") (name "unconnected-(J4-Pad1)") (class "Default")
      (node (ref "J4") (pin "1") (pinfunction "1_1") (pintype "passive"))
    )
    (net (code "62") (name "unconnected-(K1-NO1-Pad3)") (class "Default")
      (node (ref "K1") (pin "3") (pinfunction "NO1_3") (pintype "passive"))
    )
    (net (code "63") (name "unconnected-(K1-NO2-Pad4)") (class "Default")
      (node (ref "K1") (pin "4") (pinfunction "NO2_4") (pintype "passive"))
    )
    (net (code "64") (name "unconnected-(USB-CC1(A5)-Pad4)") (class "Default")
      (node (ref "USB") (pin "4") (pinfunction "CC1(A5)_4") (pintype "passive"))
    )
    (net (code "65") (name "unconnected-(USB-CC2(B5)-Pad10)") (class "Default")
      (node (ref "USB") (pin "10") (pinfunction "CC2(B5)_10") (pintype "passive"))
    )
    (net (code "66") (name "unconnected-(USB-D+1(A6)-Pad6)") (class "Default")
      (node (ref "USB") (pin "6") (pinfunction "D+1(A6)_6") (pintype "passive"))
    )
    (net (code "67") (name "unconnected-(USB-D+2(B6)-Pad8)") (class "Default")
      (node (ref "USB") (pin "8") (pinfunction "D+2(B6)_8") (pintype "passive"))
    )
    (net (code "68") (name "unconnected-(USB-D-1(A7)-Pad7)") (class "Default")
      (node (ref "USB") (pin "7") (pinfunction "D-1(A7)_7") (pintype "passive"))
    )
    (net (code "69") (name "unconnected-(USB-D-2(B7)-Pad5)") (class "Default")
      (node (ref "USB") (pin "5") (pinfunction "D-2(B7)_5") (pintype "passive"))
    )
    (net (code "70") (name "unconnected-(USB-SBU1(A8)-Pad9)") (class "Default")
      (node (ref "USB") (pin "9") (pinfunction "SBU1(A8)_9") (pintype "passive"))
    )
    (net (code "71") (name "unconnected-(USB-SBU2(B8)-Pad3)") (class "Default")
      (node (ref "USB") (pin "3") (pinfunction "SBU2(B8)_3") (pintype "passive"))
    )
    (net (code "72") (name "unconnected-(USB-Shield1-PadSH1)") (class "Default")
      (node (ref "USB") (pin "SH1") (pinfunction "Shield1_SH1") (pintype "passive"))
    )
    (net (code "73") (name "unconnected-(USB-Shield2-PadSH2)") (class "Default")
      (node (ref "USB") (pin "SH2") (pinfunction "Shield2_SH2") (pintype "passive"))
    )
    (net (code "74") (name "unconnected-(USB-Shield3-PadSH3)") (class "Default")
      (node (ref "USB") (pin "SH3") (pinfunction "Shield3_SH3") (pintype "passive"))
    )
    (net (code "75") (name "unconnected-(USB-Shield4-PadSH4)") (class "Default")
      (node (ref "USB") (pin "SH4") (pinfunction "Shield4_SH4") (pintype "passive"))
    )
  )
)
